# Connectors.net
KiCad netlist of a schematic drawn in Altium Designer
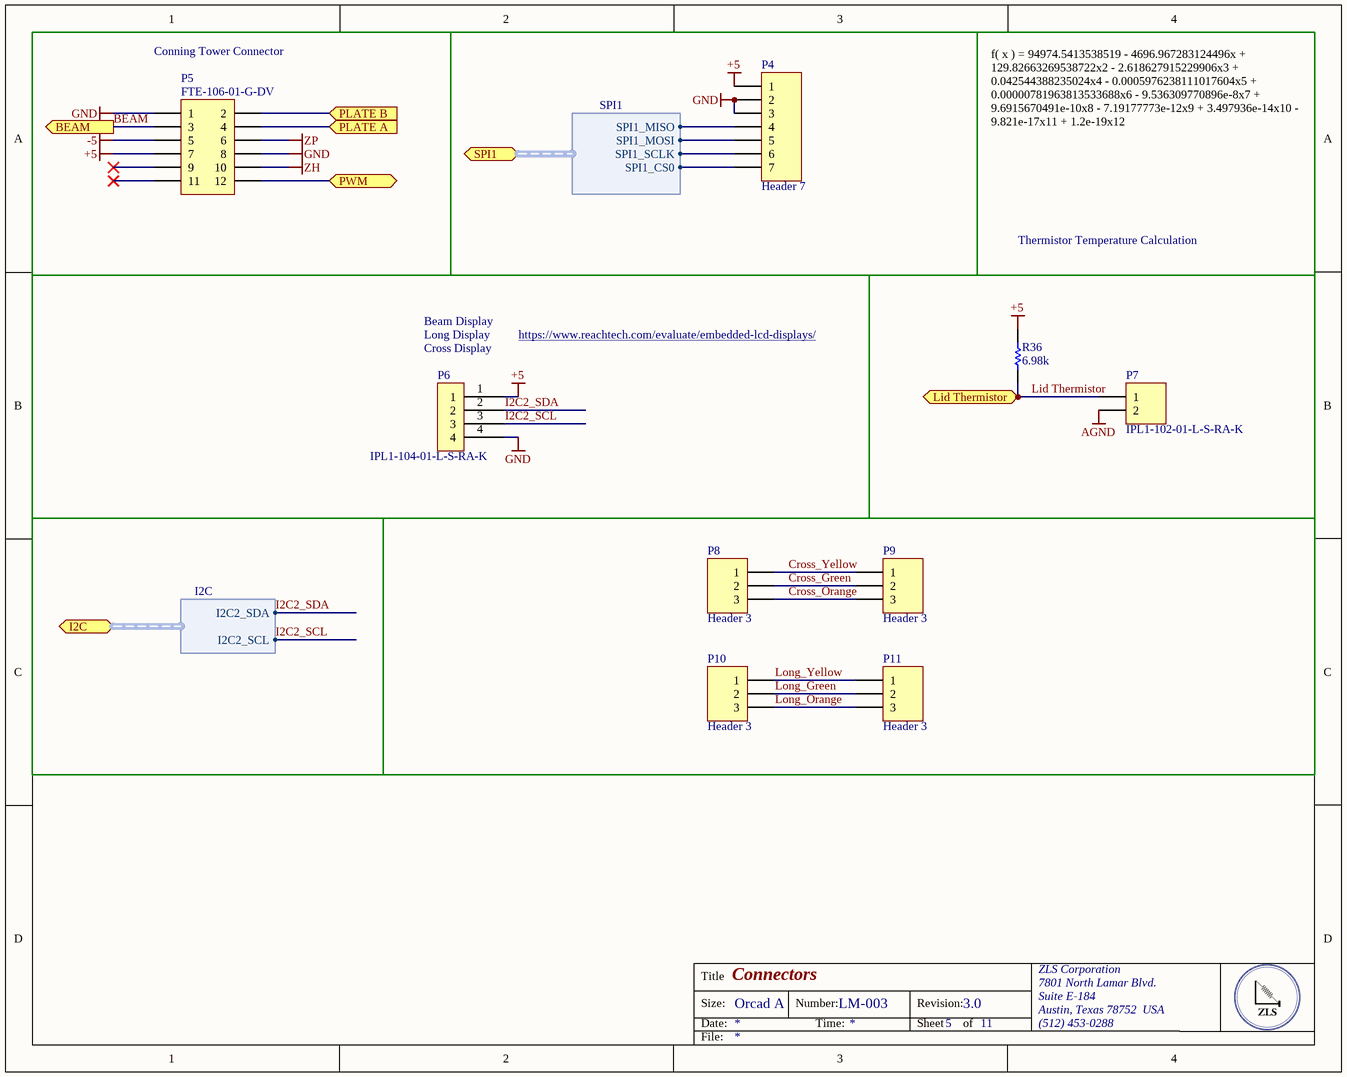
[diagram p0: Connectors.SchDoc]

(export (version "E")
  (design (tool "Eeschema 10.0.6"))
  (components
    (comp (ref "P4")
      (value "Header 7")
      (footprint "HDR1X7")
      (description "Header, 7-Pin")
      (fields (field (name "PUBLISHER") "Altium Limited"))
      (libsource (lib "Miscellaneous Connectors") (part "Header 7"))
    )
    (comp (ref "P5")
      (value "FTE-106-01-G-DV")
      (footprint "FTSH-106-01")
      (description "Header, 6-Pin, Dual row")
      (fields (field (name "MANUFACTURER") "Samtec") (field (name "PUBLISHER") "Altium Limited"))
      (libsource (lib "Conning Tower Adapter") (part "Header 6X2"))
    )
    (comp (ref "P6")
      (value "IPL1-104-01-L-S-RA-K")
      (footprint "IPL1-104-01")
      (description ".100 TERMINAL ASSY")
      (libsource (lib "ZLS_LIB") (part "53047-0410"))
    )
    (comp (ref "P7")
      (value "IPL1-102-01-L-S-RA-K")
      (footprint "IPL1-102-01")
      (description "CONN SHROUDED PWR HEADER 2POS")
      (libsource (lib "Miscellaneous Connectors") (part "Header 2H"))
    )
    (comp (ref "P8")
      (value "Header 3")
      (footprint "HDR1X3")
      (description "Header, 3-Pin")
      (fields (field (name "PUBLISHER") "Altium Limited"))
      (libsource (lib "") (part "Header 3_1"))
    )
    (comp (ref "P9")
      (value "Header 3")
      (footprint "HDR1X3")
      (description "Header, 3-Pin")
      (fields (field (name "PUBLISHER") "Altium Limited"))
      (libsource (lib "Miscellaneous Connectors") (part "Header 3"))
    )
    (comp (ref "P10")
      (value "Header 3")
      (footprint "HDR1X3")
      (description "Header, 3-Pin")
      (fields (field (name "PUBLISHER") "Altium Limited"))
      (libsource (lib "") (part "Header 3_1"))
    )
    (comp (ref "P11")
      (value "Header 3")
      (footprint "HDR1X3")
      (description "Header, 3-Pin")
      (fields (field (name "PUBLISHER") "Altium Limited"))
      (libsource (lib "Miscellaneous Connectors") (part "Header 3"))
    )
    (comp (ref "R36")
      (value "6K98 1% 0805(2012)")
      (footprint "RESC0805(2012)_N")
      (description "6K98 0.125W 1% 0805 (2012 Metric)  SMD")
      (fields
        (field (name "MANUFACTURER") "Vishay Dale")
        (field (name "MANUFACTURER PART NUMBER") "CRCW08056K98FKEA")
        (field (name "RESISTANCE (OHMS)") "6.98k")
      )
      (libsource (lib "Altium Content Vault") (part "CMP-1013-00606-1"))
    )
  )
  (nets
    (net (code "3") (name "+5") (class "Default")
      (node (ref "P4") (pin "1") (pinfunction "1_1") (pintype "passive"))
      (node (ref "P5") (pin "7") (pinfunction "7_7") (pintype "passive"))
      (node (ref "P6") (pin "1") (pinfunction "1_1") (pintype "passive"))
      (node (ref "R36") (pin "2") (pinfunction "2_2") (pintype "passive"))
    )
    (net (code "4") (name "-5") (class "Default")
      (node (ref "P5") (pin "5") (pinfunction "5_5") (pintype "passive"))
    )
    (net (code "5") (name "/BEAM") (class "Default")
      (node (ref "P5") (pin "3") (pinfunction "3_3") (pintype "passive"))
    )
    (net (code "6") (name "/Cross_Green") (class "Default")
      (node (ref "P8") (pin "2") (pinfunction "2_2") (pintype "passive"))
      (node (ref "P9") (pin "2") (pinfunction "2_2") (pintype "passive"))
    )
    (net (code "7") (name "/Cross_Orange") (class "Default")
      (node (ref "P8") (pin "3") (pinfunction "3_3") (pintype "passive"))
      (node (ref "P9") (pin "3") (pinfunction "3_3") (pintype "passive"))
    )
    (net (code "8") (name "/Cross_Yellow") (class "Default")
      (node (ref "P8") (pin "1") (pinfunction "1_1") (pintype "passive"))
      (node (ref "P9") (pin "1") (pinfunction "1_1") (pintype "passive"))
    )
    (net (code "9") (name "/I2C2_SCL") (class "Default")
      (node (ref "P6") (pin "3") (pinfunction "3_3") (pintype "passive"))
    )
    (net (code "10") (name "/I2C2_SDA") (class "Default")
      (node (ref "P6") (pin "2") (pinfunction "2_2") (pintype "passive"))
    )
    (net (code "11") (name "/Lid Thermistor") (class "Default")
      (node (ref "P7") (pin "1") (pinfunction "1_1") (pintype "passive"))
      (node (ref "R36") (pin "1") (pinfunction "1_1") (pintype "passive"))
    )
    (net (code "12") (name "/Long_Green") (class "Default")
      (node (ref "P10") (pin "2") (pinfunction "2_2") (pintype "passive"))
      (node (ref "P11") (pin "2") (pinfunction "2_2") (pintype "passive"))
    )
    (net (code "13") (name "/Long_Orange") (class "Default")
      (node (ref "P10") (pin "3") (pinfunction "3_3") (pintype "passive"))
      (node (ref "P11") (pin "3") (pinfunction "3_3") (pintype "passive"))
    )
    (net (code "14") (name "/Long_Yellow") (class "Default")
      (node (ref "P10") (pin "1") (pinfunction "1_1") (pintype "passive"))
      (node (ref "P11") (pin "1") (pinfunction "1_1") (pintype "passive"))
    )
    (net (code "15") (name "/PLATE A") (class "Default")
      (node (ref "P5") (pin "4") (pinfunction "4_4") (pintype "passive"))
    )
    (net (code "16") (name "/PLATE B") (class "Default")
      (node (ref "P5") (pin "2") (pinfunction "2_2") (pintype "passive"))
    )
    (net (code "17") (name "/PWM") (class "Default")
      (node (ref "P5") (pin "12") (pinfunction "12_12") (pintype "passive"))
    )
    (net (code "18") (name "/SPI1_CS0") (class "Default")
      (node (ref "P4") (pin "7") (pinfunction "7_7") (pintype "passive"))
    )
    (net (code "19") (name "/SPI1_MISO") (class "Default")
      (node (ref "P4") (pin "4") (pinfunction "4_4") (pintype "passive"))
    )
    (net (code "20") (name "/SPI1_MOSI") (class "Default")
      (node (ref "P4") (pin "5") (pinfunction "5_5") (pintype "passive"))
    )
    (net (code "21") (name "/SPI1_SCLK") (class "Default")
      (node (ref "P4") (pin "6") (pinfunction "6_6") (pintype "passive"))
    )
    (net (code "24") (name "AGND") (class "Default")
      (node (ref "P7") (pin "2") (pinfunction "2_2") (pintype "passive"))
    )
    (net (code "25") (name "GND") (class "Default")
      (node (ref "P4") (pin "2") (pinfunction "2_2") (pintype "passive"))
      (node (ref "P4") (pin "3") (pinfunction "3_3") (pintype "passive"))
      (node (ref "P5") (pin "1") (pinfunction "1_1") (pintype "passive"))
      (node (ref "P5") (pin "8") (pinfunction "8_8") (pintype "passive"))
      (node (ref "P6") (pin "4") (pinfunction "4_4") (pintype "passive"))
    )
    (net (code "26") (name "ZH") (class "Default")
      (node (ref "P5") (pin "10") (pinfunction "10_10") (pintype "passive"))
    )
    (net (code "27") (name "ZP") (class "Default")
      (node (ref "P5") (pin "6") (pinfunction "6_6") (pintype "passive"))
    )
    (net (code "28") (name "unconnected-(P5-Pad9)") (class "Default")
      (node (ref "P5") (pin "9") (pinfunction "9_9") (pintype "passive+no_connect"))
    )
    (net (code "29") (name "unconnected-(P5-Pad11)") (class "Default")
      (node (ref "P5") (pin "11") (pinfunction "11_11") (pintype "passive+no_connect"))
    )
  )
)
